# Meaty_3__vPS03.net
KiCad netlist of a schematic drawn in EAGLE
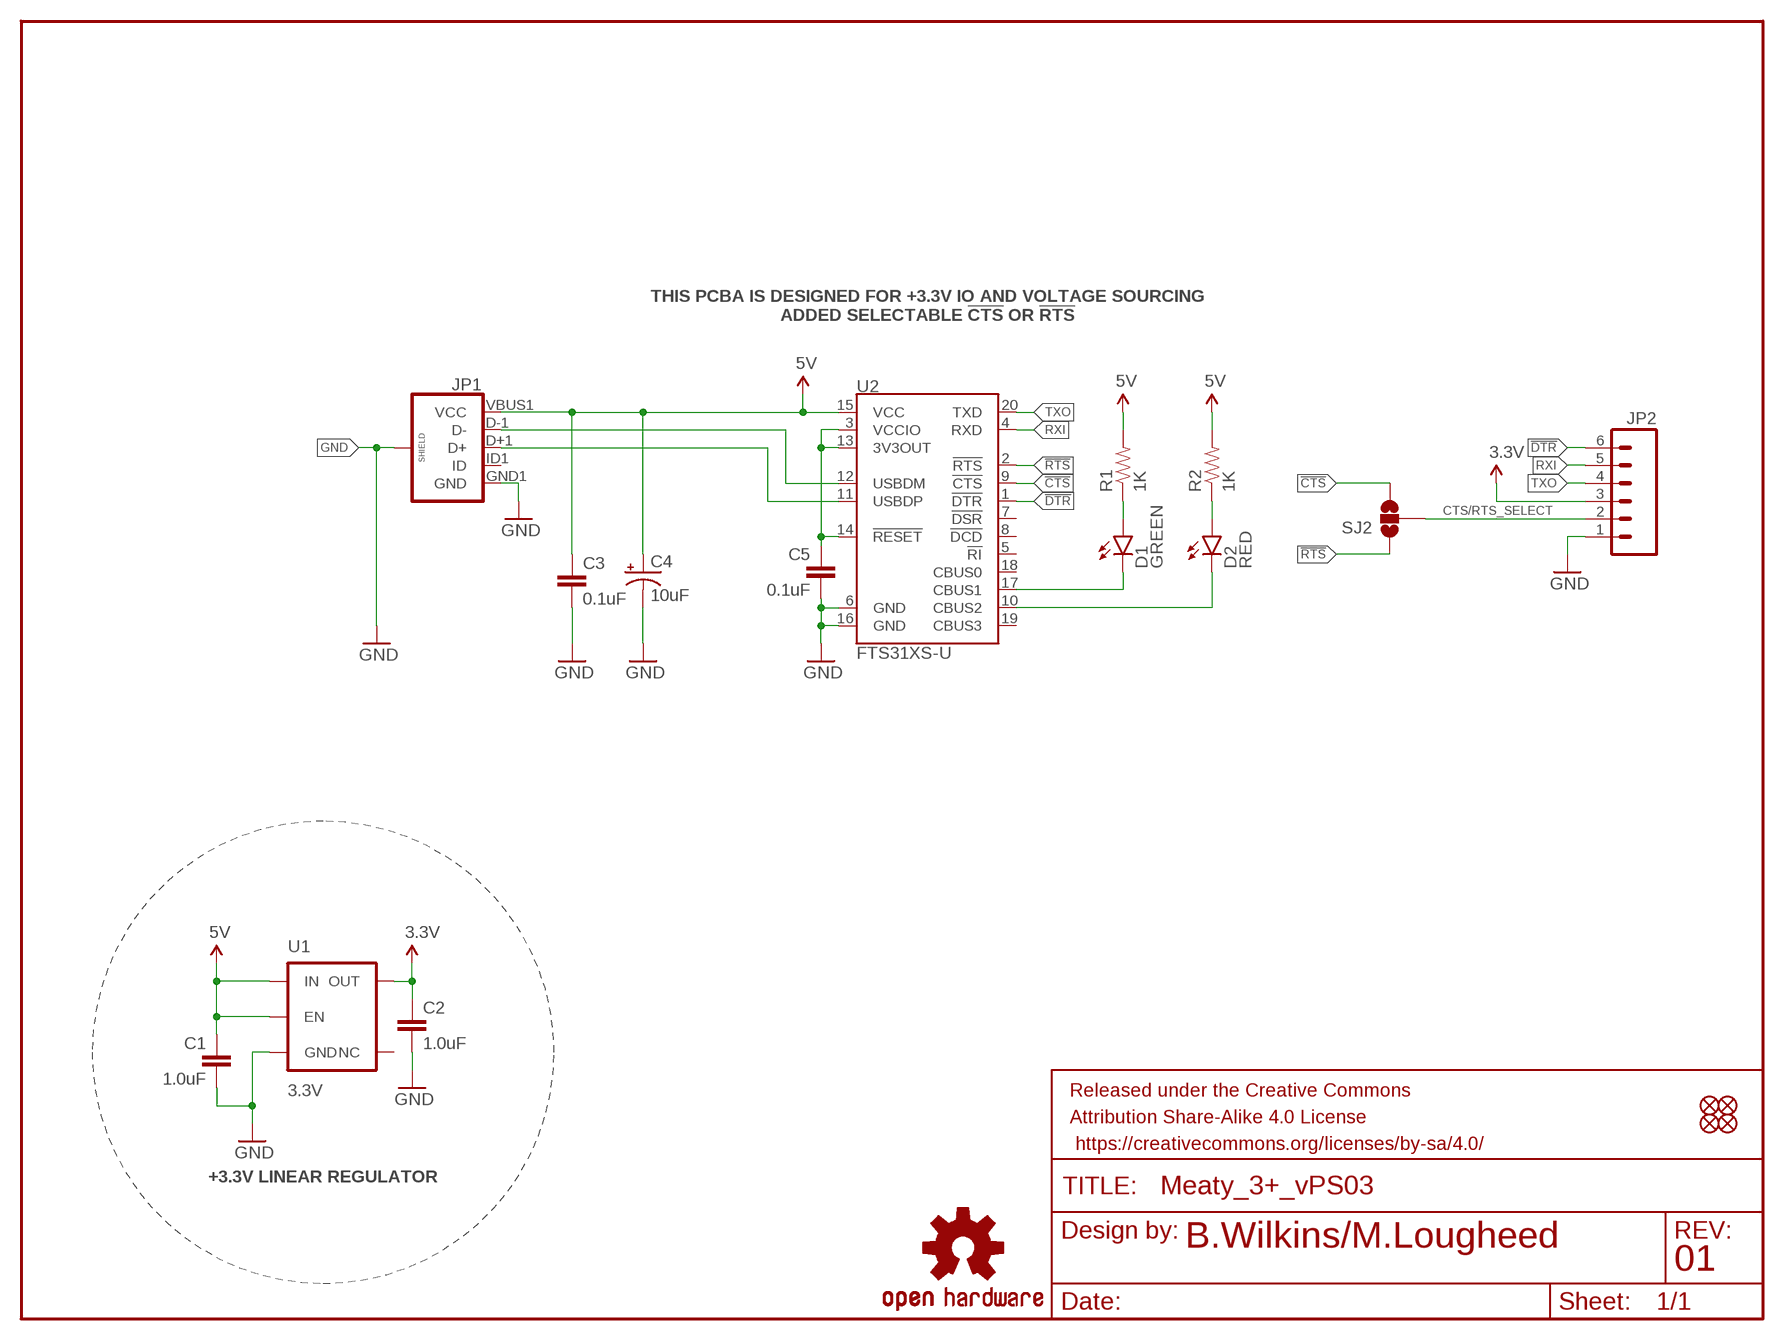
[diagram p0: schematic, sheet 1]

(export (version "E")
  (design (tool "Eeschema 10.0.6"))
  (components
    (comp (ref "C1")
      (value "1.0uF")
      (footprint "eagle-import:0603-CAP")
      (libsource (lib "eagle-import") (part "1.0UF-16V-10%(0603)"))
    )
    (comp (ref "C2")
      (value "1.0uF")
      (footprint "eagle-import:0603-CAP")
      (libsource (lib "eagle-import") (part "1.0UF-16V-10%(0603)"))
    )
    (comp (ref "C3")
      (value "0.1uF")
      (footprint "eagle-import:0603-CAP")
      (libsource (lib "eagle-import") (part "0.1UF-25V(+80/-20%)(0603)"))
    )
    (comp (ref "C4")
      (value "10uF")
      (footprint "eagle-import:EIA3216")
      (libsource (lib "eagle-import") (part "10UF-16V-10%(TANT)"))
    )
    (comp (ref "C5")
      (value "0.1uF")
      (footprint "eagle-import:0603-CAP")
      (libsource (lib "eagle-import") (part "0.1UF-25V(+80/-20%)(0603)"))
    )
    (comp (ref "D1")
      (value "GREEN")
      (footprint "eagle-import:LED-0603")
      (libsource (lib "eagle-import") (part "LED-GREEN0603"))
    )
    (comp (ref "D2")
      (value "RED")
      (footprint "eagle-import:LED-0603")
      (libsource (lib "eagle-import") (part "LED-RED0603"))
    )
    (comp (ref "FRAME1")
      (value "FRAME-LETTER")
      (footprint "eagle-import:CREATIVE_COMMONS")
      (libsource (lib "eagle-import") (part "FRAME-LETTER"))
    )
    (comp (ref "JP1")
      (value "USB_MICROB_PLUGWE629105136821")
      (footprint "eagle-import:MICRO-USB-2.0-B-SMT")
      (libsource (lib "eagle-import") (part "USB_MICROB_PLUGWE629105136821"))
    )
    (comp (ref "JP2")
      (value "M06SMD-FEMALE-V2")
      (footprint "eagle-import:1X06-SMD-FEMALE-V2")
      (libsource (lib "eagle-import") (part "M06SMD-FEMALE-V2"))
    )
    (comp (ref "JP3")
      (value "FIDUCIAL1X2")
      (footprint "eagle-import:FIDUCIAL-1X2")
      (libsource (lib "eagle-import") (part "FIDUCIAL1X2"))
    )
    (comp (ref "JP4")
      (value "FIDUCIAL1X2")
      (footprint "eagle-import:FIDUCIAL-1X2")
      (libsource (lib "eagle-import") (part "FIDUCIAL1X2"))
    )
    (comp (ref "JP5")
      (value "FIDUCIAL1X2")
      (footprint "eagle-import:FIDUCIAL-1X2")
      (libsource (lib "eagle-import") (part "FIDUCIAL1X2"))
    )
    (comp (ref "JP6")
      (value "FIDUCIAL1X2")
      (footprint "eagle-import:FIDUCIAL-1X2")
      (libsource (lib "eagle-import") (part "FIDUCIAL1X2"))
    )
    (comp (ref "LOGO1")
      (value "OSHW-LOGOS")
      (footprint "eagle-import:OSHW-LOGO-S")
      (libsource (lib "eagle-import") (part "OSHW-LOGOS"))
    )
    (comp (ref "R1")
      (value "1K")
      (footprint "eagle-import:0603-RES")
      (libsource (lib "eagle-import") (part "1KOHM-1/10W-1%(0603)"))
    )
    (comp (ref "R2")
      (value "1K")
      (footprint "eagle-import:0603-RES")
      (libsource (lib "eagle-import") (part "1KOHM-1/10W-1%(0603)"))
    )
    (comp (ref "SJ2")
      (value "SOLDERJUMPER_2WAYS")
      (footprint "eagle-import:SJ_3")
      (libsource (lib "eagle-import") (part "SOLDERJUMPER_2WAYS"))
    )
    (comp (ref "U1")
      (value "3.3V")
      (footprint "eagle-import:SOT23-5")
      (libsource (lib "eagle-import") (part "V_REG_AP2112K-3.3V"))
    )
    (comp (ref "U2")
      (value "FTS31XS-U")
      (footprint "eagle-import:SSOP20_L")
      (libsource (lib "eagle-import") (part "FT231XS"))
    )
  )
  (nets
    (net (code "1") (name "/CTS{slash}RTS_SELECT") (class "Default")
      (node (ref "JP2") (pin "2") (pinfunction "2_2") (pintype "passive"))
      (node (ref "SJ2") (pin "2") (pinfunction "2_2") (pintype "passive"))
    )
    (net (code "2") (name "/~{CTS}") (class "Default")
      (node (ref "SJ2") (pin "3") (pinfunction "3_3") (pintype "passive"))
      (node (ref "U2") (pin "9") (pinfunction "~{CTS}_9") (pintype "bidirectional"))
    )
    (net (code "3") (name "/~{DTR}") (class "Default")
      (node (ref "JP2") (pin "6") (pinfunction "6_6") (pintype "passive"))
      (node (ref "U2") (pin "1") (pinfunction "~{DTR}_1") (pintype "bidirectional"))
    )
    (net (code "4") (name "/~{RTS}") (class "Default")
      (node (ref "SJ2") (pin "1") (pinfunction "1_1") (pintype "passive"))
      (node (ref "U2") (pin "2") (pinfunction "~{RTS}_2") (pintype "bidirectional"))
    )
    (net (code "5") (name "3.3V") (class "Default")
      (node (ref "C2") (pin "1") (pinfunction "1_1") (pintype "passive"))
      (node (ref "JP2") (pin "3") (pinfunction "3_3") (pintype "passive"))
      (node (ref "U1") (pin "5") (pinfunction "OUT_5") (pintype "passive"))
    )
    (net (code "6") (name "5V") (class "Default")
      (node (ref "C1") (pin "1") (pinfunction "1_1") (pintype "passive"))
      (node (ref "C3") (pin "1") (pinfunction "1_1") (pintype "passive"))
      (node (ref "C4") (pin "A") (pinfunction "+_A") (pintype "passive"))
      (node (ref "JP1") (pin "VBUS1") (pinfunction "VCC_VBUS1") (pintype "bidirectional"))
      (node (ref "R1") (pin "2") (pinfunction "2_2") (pintype "passive"))
      (node (ref "R2") (pin "2") (pinfunction "2_2") (pintype "passive"))
      (node (ref "U1") (pin "1") (pinfunction "IN_1") (pintype "input"))
      (node (ref "U1") (pin "3") (pinfunction "EN_3") (pintype "input"))
      (node (ref "U2") (pin "15") (pinfunction "VCC_15") (pintype "bidirectional"))
    )
    (net (code "7") (name "GND") (class "Default")
      (node (ref "C1") (pin "2") (pinfunction "2_2") (pintype "passive"))
      (node (ref "C2") (pin "2") (pinfunction "2_2") (pintype "passive"))
      (node (ref "C3") (pin "2") (pinfunction "2_2") (pintype "passive"))
      (node (ref "C4") (pin "C") (pinfunction "-_C") (pintype "passive"))
      (node (ref "C5") (pin "2") (pinfunction "2_2") (pintype "passive"))
      (node (ref "JP1") (pin "GND1") (pinfunction "GND_GND1") (pintype "bidirectional"))
      (node (ref "JP1") (pin "SHIELD0") (pinfunction "SHIELD_SHIELD0") (pintype "bidirectional"))
      (node (ref "JP1") (pin "SHIELD1") (pinfunction "SHIELD_SHIELD1") (pintype "bidirectional"))
      (node (ref "JP1") (pin "SHIELD3") (pinfunction "SHIELD_SHIELD3") (pintype "bidirectional"))
      (node (ref "JP2") (pin "1") (pinfunction "1_1") (pintype "passive"))
      (node (ref "U1") (pin "2") (pinfunction "GND_2") (pintype "input"))
      (node (ref "U2") (pin "16") (pinfunction "GND_16") (pintype "bidirectional"))
      (node (ref "U2") (pin "6") (pinfunction "GND_6") (pintype "bidirectional"))
    )
    (net (code "8") (name "Net-(D1-PadA)") (class "Default")
      (node (ref "D1") (pin "A") (pinfunction "A_A") (pintype "passive"))
      (node (ref "R1") (pin "1") (pinfunction "1_1") (pintype "passive"))
    )
    (net (code "9") (name "Net-(D2-PadA)") (class "Default")
      (node (ref "D2") (pin "A") (pinfunction "A_A") (pintype "passive"))
      (node (ref "R2") (pin "1") (pinfunction "1_1") (pintype "passive"))
    )
    (net (code "10") (name "Net-(JP1-D+)") (class "Default")
      (node (ref "JP1") (pin "D+1") (pinfunction "D+_D+1") (pintype "bidirectional"))
      (node (ref "U2") (pin "11") (pinfunction "USBDP_11") (pintype "bidirectional"))
    )
    (net (code "11") (name "Net-(JP1-D-)") (class "Default")
      (node (ref "JP1") (pin "D-1") (pinfunction "D-_D-1") (pintype "bidirectional"))
      (node (ref "U2") (pin "12") (pinfunction "USBDM_12") (pintype "bidirectional"))
    )
    (net (code "12") (name "Net-(U2-3V3OUT)") (class "Default")
      (node (ref "C5") (pin "1") (pinfunction "1_1") (pintype "passive"))
      (node (ref "U2") (pin "13") (pinfunction "3V3OUT_13") (pintype "bidirectional"))
      (node (ref "U2") (pin "14") (pinfunction "~{RESET}_14") (pintype "bidirectional"))
      (node (ref "U2") (pin "3") (pinfunction "VCCIO_3") (pintype "bidirectional"))
    )
    (net (code "13") (name "Net-(U2-CBUS1)") (class "Default")
      (node (ref "D1") (pin "C") (pinfunction "C_C") (pintype "passive"))
      (node (ref "U2") (pin "17") (pinfunction "CBUS1_17") (pintype "bidirectional"))
    )
    (net (code "14") (name "Net-(U2-CBUS2)") (class "Default")
      (node (ref "D2") (pin "C") (pinfunction "C_C") (pintype "passive"))
      (node (ref "U2") (pin "10") (pinfunction "CBUS2_10") (pintype "bidirectional"))
    )
    (net (code "15") (name "RXI") (class "Default")
      (node (ref "JP2") (pin "5") (pinfunction "5_5") (pintype "passive"))
      (node (ref "U2") (pin "4") (pinfunction "RXD_4") (pintype "bidirectional"))
    )
    (net (code "16") (name "TXO") (class "Default")
      (node (ref "JP2") (pin "4") (pinfunction "4_4") (pintype "passive"))
      (node (ref "U2") (pin "20") (pinfunction "TXD_20") (pintype "bidirectional"))
    )
    (net (code "17") (name "unconnected-(JP1-ID-PadID1)") (class "Default")
      (node (ref "JP1") (pin "ID1") (pinfunction "ID_ID1") (pintype "bidirectional"))
    )
    (net (code "18") (name "unconnected-(U1-NC-Pad4)") (class "Default")
      (node (ref "U1") (pin "4") (pinfunction "NC_4") (pintype "input"))
    )
    (net (code "19") (name "unconnected-(U2-CBUS0-Pad18)") (class "Default")
      (node (ref "U2") (pin "18") (pinfunction "CBUS0_18") (pintype "bidirectional"))
    )
    (net (code "20") (name "unconnected-(U2-CBUS3-Pad19)") (class "Default")
      (node (ref "U2") (pin "19") (pinfunction "CBUS3_19") (pintype "bidirectional"))
    )
    (net (code "21") (name "unconnected-(U2-~{DCD}-Pad8)") (class "Default")
      (node (ref "U2") (pin "8") (pinfunction "~{DCD}_8") (pintype "bidirectional"))
    )
    (net (code "22") (name "unconnected-(U2-~{DSR}-Pad7)") (class "Default")
      (node (ref "U2") (pin "7") (pinfunction "~{DSR}_7") (pintype "bidirectional"))
    )
    (net (code "23") (name "unconnected-(U2-~{RI}-Pad5)") (class "Default")
      (node (ref "U2") (pin "5") (pinfunction "~{RI}_5") (pintype "bidirectional"))
    )
  )
)
